# miniDMXplayer.net
KiCad netlist of a schematic drawn in EAGLE
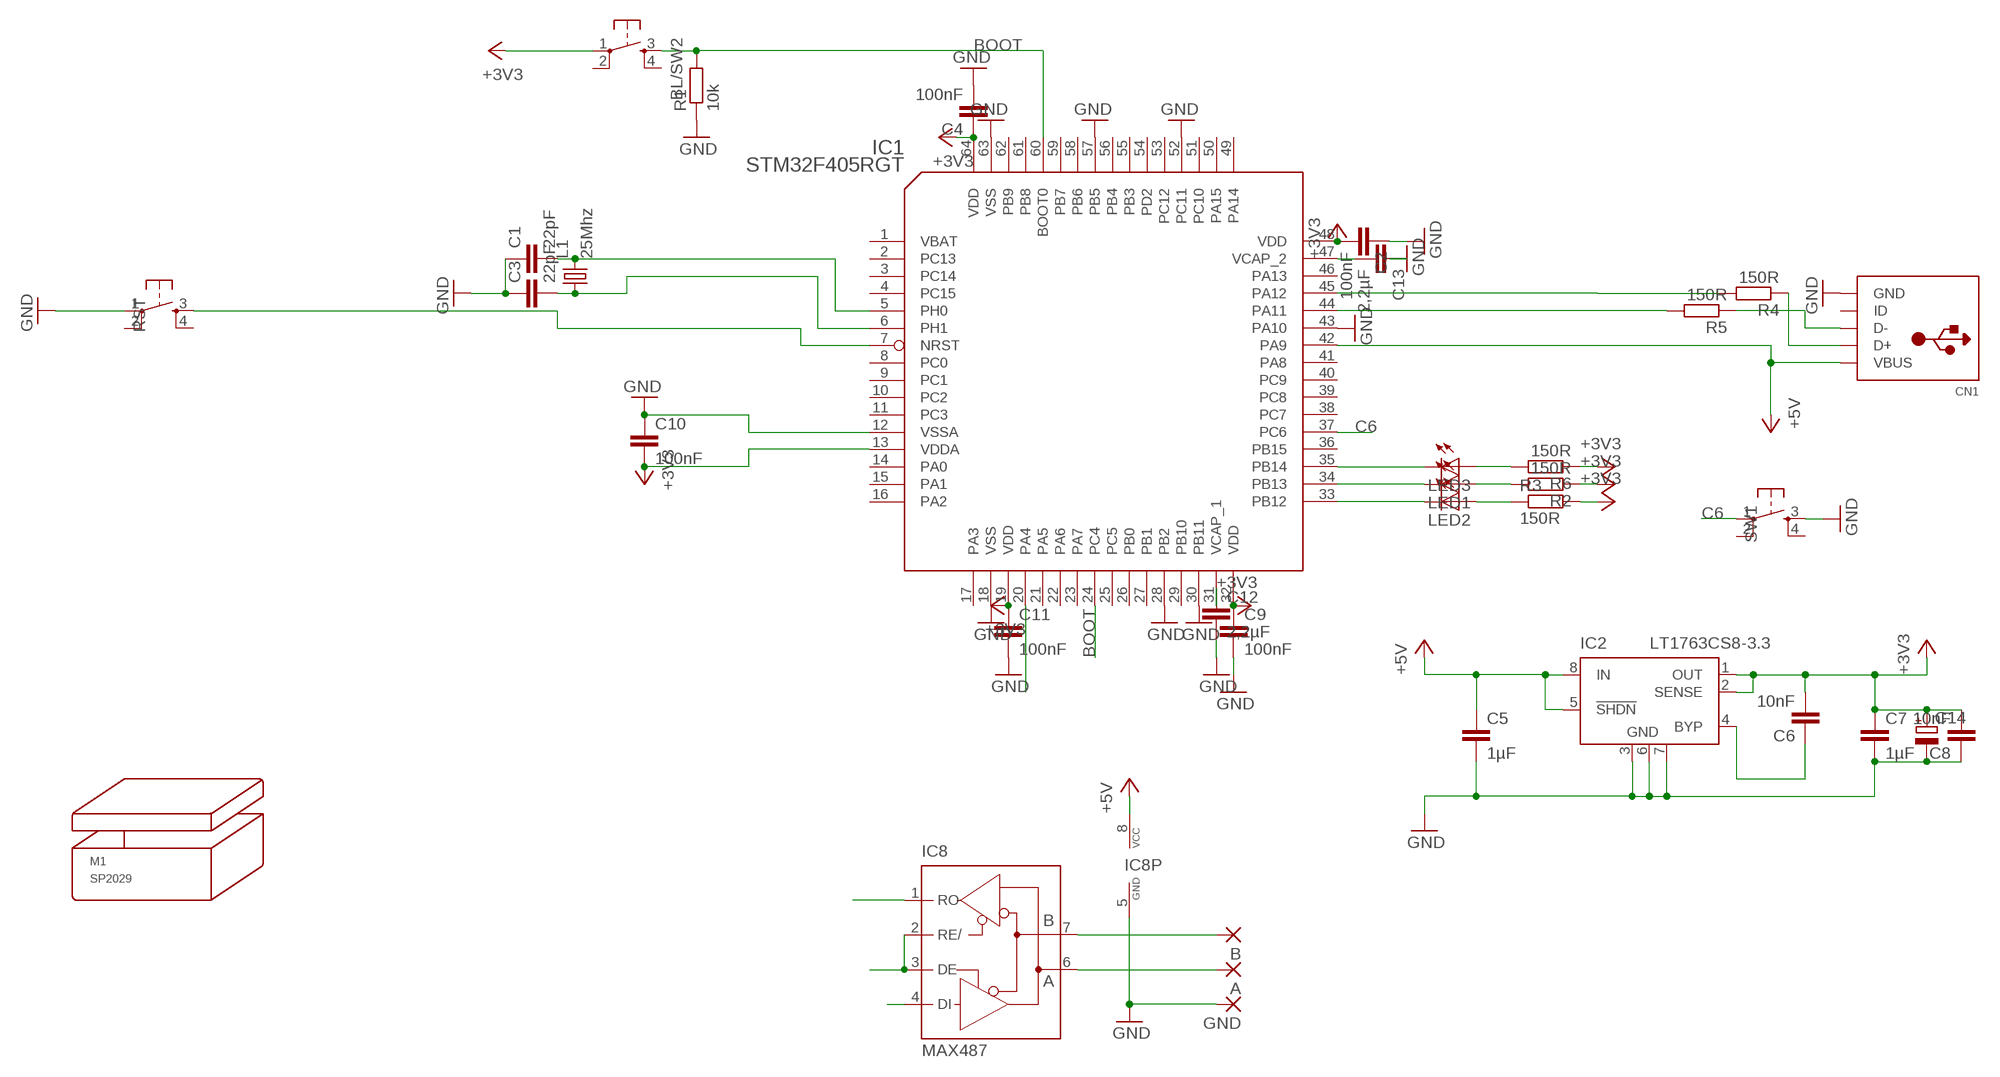
[diagram p0: schematic, sheet 1]

(export (version "E")
  (design (tool "Eeschema 10.0.6"))
  (components
    (comp (ref "A")
      (value "SMD5")
      (footprint "eagle-import:SMD2,54-5,08")
      (libsource (lib "eagle-import") (part "SMD5"))
    )
    (comp (ref "B")
      (value "SMD5")
      (footprint "eagle-import:SMD2,54-5,08")
      (libsource (lib "eagle-import") (part "SMD5"))
    )
    (comp (ref "BL/SW2")
      (value "DTSM-6")
      (footprint "eagle-import:DTSM-6")
      (libsource (lib "eagle-import") (part "DTSM-6"))
    )
    (comp (ref "C1")
      (value "22pF")
      (footprint "eagle-import:C0402")
      (libsource (lib "eagle-import") (part "C-EUC0402"))
    )
    (comp (ref "C2")
      (value "100nF")
      (footprint "eagle-import:C0402")
      (libsource (lib "eagle-import") (part "C-EUC0402"))
    )
    (comp (ref "C3")
      (value "22pF")
      (footprint "eagle-import:C0402")
      (libsource (lib "eagle-import") (part "C-EUC0402"))
    )
    (comp (ref "C4")
      (value "100nF")
      (footprint "eagle-import:C0402")
      (libsource (lib "eagle-import") (part "C-EUC0402"))
    )
    (comp (ref "C5")
      (value "1µF")
      (footprint "eagle-import:0805")
      (libsource (lib "eagle-import") (part "CAP0805"))
    )
    (comp (ref "C6")
      (value "10nF")
      (footprint "eagle-import:C0402")
      (libsource (lib "eagle-import") (part "C-EUC0402"))
    )
    (comp (ref "C7")
      (value "1µF")
      (footprint "eagle-import:0805")
      (libsource (lib "eagle-import") (part "CAP0805"))
    )
    (comp (ref "C8")
      (value "10nF")
      (footprint "eagle-import:C0402")
      (libsource (lib "eagle-import") (part "C-EUC0402"))
    )
    (comp (ref "C9")
      (value "100nF")
      (footprint "eagle-import:C0402")
      (libsource (lib "eagle-import") (part "C-EUC0402"))
    )
    (comp (ref "C10")
      (value "100nF")
      (footprint "eagle-import:C0402")
      (libsource (lib "eagle-import") (part "C-EUC0402"))
    )
    (comp (ref "C11")
      (value "100nF")
      (footprint "eagle-import:C0402")
      (libsource (lib "eagle-import") (part "C-EUC0402"))
    )
    (comp (ref "C12")
      (value "2,2µF")
      (footprint "eagle-import:0805")
      (libsource (lib "eagle-import") (part "CAP0805"))
    )
    (comp (ref "C13")
      (value "2,2µF")
      (footprint "eagle-import:0805")
      (libsource (lib "eagle-import") (part "CAP0805"))
    )
    (comp (ref "C14")
      (value "CPOL-EUSMCA")
      (footprint "eagle-import:SMC_A")
      (libsource (lib "eagle-import") (part "CPOL-EUSMCA"))
    )
    (comp (ref "CN1")
      (value "USBMINIB")
      (footprint "eagle-import:USB-MINIB")
      (libsource (lib "eagle-import") (part "USBMINIB"))
    )
    (comp (ref "GND")
      (value "SMD5")
      (footprint "eagle-import:SMD2,54-5,08")
      (libsource (lib "eagle-import") (part "SMD5"))
    )
    (comp (ref "IC1")
      (value "STM32F405RGT")
      (footprint "eagle-import:LQFP64")
      (libsource (lib "eagle-import") (part "STM32F405RTG"))
    )
    (comp (ref "IC2")
      (value "LT1763CS8-3.3")
      (footprint "eagle-import:SOIC8")
      (libsource (lib "eagle-import") (part "LT1763CS8-3.3"))
    )
    (comp (ref "IC8")
      (value "MAX487")
      (footprint "eagle-import:SO08")
      (fields (field (name "MF") "MAXIM") (field (name "MPN") "MAX481CSA"))
      (libsource (lib "eagle-import") (part "MAX481CSA"))
    )
    (comp (ref "L1")
      (value "25Mhz")
      (footprint "eagle-import:X22")
      (libsource (lib "eagle-import") (part "X22-OSCILLATOR"))
    )
    (comp (ref "LED1")
      (value "LED0603")
      (footprint "eagle-import:LED-0603")
      (libsource (lib "eagle-import") (part "LED0603"))
    )
    (comp (ref "LED2")
      (value "LED0603")
      (footprint "eagle-import:LED-0603")
      (libsource (lib "eagle-import") (part "LED0603"))
    )
    (comp (ref "LED3")
      (value "LED0603")
      (footprint "eagle-import:LED-0603")
      (libsource (lib "eagle-import") (part "LED0603"))
    )
    (comp (ref "M1")
      (value "SP2029")
      (footprint "eagle-import:SP2029")
      (libsource (lib "eagle-import") (part "SP2029"))
    )
    (comp (ref "R1")
      (value "10k")
      (footprint "eagle-import:R0402")
      (libsource (lib "eagle-import") (part "R-EU_R0402"))
    )
    (comp (ref "R2")
      (value "150R")
      (footprint "eagle-import:R0402")
      (libsource (lib "eagle-import") (part "R-EU_R0402"))
    )
    (comp (ref "R3")
      (value "150R")
      (footprint "eagle-import:R0402")
      (libsource (lib "eagle-import") (part "R-EU_R0402"))
    )
    (comp (ref "R4")
      (value "150R")
      (footprint "eagle-import:R0402")
      (libsource (lib "eagle-import") (part "R-EU_R0402"))
    )
    (comp (ref "R5")
      (value "150R")
      (footprint "eagle-import:R0402")
      (libsource (lib "eagle-import") (part "R-EU_R0402"))
    )
    (comp (ref "R6")
      (value "150R")
      (footprint "eagle-import:R0402")
      (libsource (lib "eagle-import") (part "R-EU_R0402"))
    )
    (comp (ref "RST")
      (value "DTSM-6")
      (footprint "eagle-import:DTSM-6")
      (libsource (lib "eagle-import") (part "DTSM-6"))
    )
    (comp (ref "SW1")
      (value "DTSM-6")
      (footprint "eagle-import:DTSM-6")
      (libsource (lib "eagle-import") (part "DTSM-6"))
    )
  )
  (nets
    (net (code "1") (name "+3V3") (class "Default")
      (node (ref "BL/SW2") (pin "1") (pinfunction "1_1") (pintype "passive"))
      (node (ref "C10") (pin "2") (pinfunction "2_2") (pintype "passive"))
      (node (ref "C11") (pin "1") (pinfunction "1_1") (pintype "passive"))
      (node (ref "C14") (pin "+") (pinfunction "+_+") (pintype "passive"))
      (node (ref "C2") (pin "2") (pinfunction "2_2") (pintype "passive"))
      (node (ref "C4") (pin "1") (pinfunction "1_1") (pintype "passive"))
      (node (ref "C6") (pin "2") (pinfunction "2_2") (pintype "passive"))
      (node (ref "C7") (pin "1") (pinfunction "1_1") (pintype "passive"))
      (node (ref "C8") (pin "2") (pinfunction "2_2") (pintype "passive"))
      (node (ref "C9") (pin "1") (pinfunction "1_1") (pintype "passive"))
      (node (ref "IC1") (pin "13") (pinfunction "VDDA_13") (pintype "power_in"))
      (node (ref "IC1") (pin "19") (pinfunction "VDD_19") (pintype "power_in"))
      (node (ref "IC1") (pin "32") (pinfunction "VDD_32") (pintype "power_in"))
      (node (ref "IC1") (pin "48") (pinfunction "VDD_48") (pintype "power_in"))
      (node (ref "IC1") (pin "64") (pinfunction "VDD_64") (pintype "power_in"))
      (node (ref "IC2") (pin "1") (pinfunction "OUT_1") (pintype "passive"))
      (node (ref "IC2") (pin "2") (pinfunction "SENSE_2") (pintype "input"))
      (node (ref "R2") (pin "1") (pinfunction "1_1") (pintype "passive"))
      (node (ref "R3") (pin "2") (pinfunction "2_2") (pintype "passive"))
      (node (ref "R6") (pin "1") (pinfunction "1_1") (pintype "passive"))
    )
    (net (code "2") (name "+5V") (class "Default")
      (node (ref "C5") (pin "1") (pinfunction "1_1") (pintype "passive"))
      (node (ref "CN1") (pin "VBUS") (pinfunction "VBUS_VBUS") (pintype "power_in"))
      (node (ref "IC1") (pin "42") (pinfunction "PA9_42") (pintype "bidirectional"))
      (node (ref "IC2") (pin "5") (pinfunction "~{SHDN}_5") (pintype "input"))
      (node (ref "IC2") (pin "8") (pinfunction "IN_8") (pintype "input"))
      (node (ref "IC8") (pin "8") (pinfunction "VCC_8") (pintype "power_in"))
    )
    (net (code "3") (name "/BOOT") (class "Default")
      (node (ref "BL/SW2") (pin "3") (pinfunction "3_3") (pintype "passive"))
      (node (ref "IC1") (pin "24") (pinfunction "PC4_24") (pintype "bidirectional"))
      (node (ref "IC1") (pin "60") (pinfunction "BOOT0_60") (pintype "bidirectional"))
      (node (ref "R1") (pin "2") (pinfunction "2_2") (pintype "passive"))
    )
    (net (code "4") (name "/C6") (class "Default")
      (node (ref "IC1") (pin "37") (pinfunction "PC6_37") (pintype "bidirectional"))
      (node (ref "SW1") (pin "1") (pinfunction "1_1") (pintype "passive"))
    )
    (net (code "5") (name "/VBAT") (class "Default")
      (node (ref "IC1") (pin "1") (pinfunction "VBAT_1") (pintype "power_in"))
    )
    (net (code "6") (name "GND") (class "Default")
      (node (ref "C1") (pin "1") (pinfunction "1_1") (pintype "passive"))
      (node (ref "C10") (pin "1") (pinfunction "1_1") (pintype "passive"))
      (node (ref "C11") (pin "2") (pinfunction "2_2") (pintype "passive"))
      (node (ref "C12") (pin "2") (pinfunction "2_2") (pintype "passive"))
      (node (ref "C13") (pin "1") (pinfunction "1_1") (pintype "passive"))
      (node (ref "C14") (pin "-") (pinfunction "-_-") (pintype "passive"))
      (node (ref "C2") (pin "1") (pinfunction "1_1") (pintype "passive"))
      (node (ref "C3") (pin "1") (pinfunction "1_1") (pintype "passive"))
      (node (ref "C4") (pin "2") (pinfunction "2_2") (pintype "passive"))
      (node (ref "C5") (pin "2") (pinfunction "2_2") (pintype "passive"))
      (node (ref "C7") (pin "2") (pinfunction "2_2") (pintype "passive"))
      (node (ref "C8") (pin "1") (pinfunction "1_1") (pintype "passive"))
      (node (ref "C9") (pin "2") (pinfunction "2_2") (pintype "passive"))
      (node (ref "CN1") (pin "GND") (pinfunction "GND_GND") (pintype "power_in"))
      (node (ref "GND") (pin "1") (pinfunction "P_1") (pintype "passive"))
      (node (ref "IC1") (pin "12") (pinfunction "VSSA_12") (pintype "power_in"))
      (node (ref "IC1") (pin "18") (pinfunction "VSS_18") (pintype "power_in"))
      (node (ref "IC1") (pin "28") (pinfunction "PB2_28") (pintype "bidirectional"))
      (node (ref "IC1") (pin "30") (pinfunction "PB11_30") (pintype "bidirectional"))
      (node (ref "IC1") (pin "43") (pinfunction "PA10_43") (pintype "bidirectional"))
      (node (ref "IC1") (pin "52") (pinfunction "PC11_52") (pintype "bidirectional"))
      (node (ref "IC1") (pin "57") (pinfunction "PB5_57") (pintype "bidirectional"))
      (node (ref "IC1") (pin "63") (pinfunction "VSS_63") (pintype "power_in"))
      (node (ref "IC2") (pin "3") (pinfunction "GND_3") (pintype "power_in"))
      (node (ref "IC2") (pin "6") (pinfunction "GND_6") (pintype "power_in"))
      (node (ref "IC2") (pin "7") (pinfunction "GND_7") (pintype "power_in"))
      (node (ref "IC8") (pin "5") (pinfunction "GND_5") (pintype "power_in"))
      (node (ref "R1") (pin "1") (pinfunction "1_1") (pintype "passive"))
      (node (ref "RST") (pin "1") (pinfunction "1_1") (pintype "passive"))
      (node (ref "SW1") (pin "3") (pinfunction "3_3") (pintype "passive"))
    )
    (net (code "7") (name "Net-(A-P)") (class "Default")
      (node (ref "A") (pin "1") (pinfunction "P_1") (pintype "passive"))
      (node (ref "IC8") (pin "6") (pinfunction "A_6") (pintype "passive"))
    )
    (net (code "8") (name "Net-(B-P)") (class "Default")
      (node (ref "B") (pin "1") (pinfunction "P_1") (pintype "passive"))
      (node (ref "IC8") (pin "7") (pinfunction "B_7") (pintype "passive"))
    )
    (net (code "9") (name "Net-(CN1-PadD+)") (class "Default")
      (node (ref "CN1") (pin "D+") (pinfunction "D+_D+") (pintype "bidirectional"))
      (node (ref "R4") (pin "1") (pinfunction "1_1") (pintype "passive"))
    )
    (net (code "10") (name "Net-(CN1-PadD-)") (class "Default")
      (node (ref "CN1") (pin "D-") (pinfunction "D-_D-") (pintype "bidirectional"))
      (node (ref "R5") (pin "1") (pinfunction "1_1") (pintype "passive"))
    )
    (net (code "11") (name "Net-(IC1-NRST)") (class "Default")
      (node (ref "IC1") (pin "7") (pinfunction "NRST_7") (pintype "input"))
      (node (ref "RST") (pin "3") (pinfunction "3_3") (pintype "passive"))
    )
    (net (code "12") (name "Net-(IC1-PA11)") (class "Default")
      (node (ref "IC1") (pin "44") (pinfunction "PA11_44") (pintype "bidirectional"))
      (node (ref "R5") (pin "2") (pinfunction "2_2") (pintype "passive"))
    )
    (net (code "13") (name "Net-(IC1-PA12)") (class "Default")
      (node (ref "IC1") (pin "45") (pinfunction "PA12_45") (pintype "bidirectional"))
      (node (ref "R4") (pin "2") (pinfunction "2_2") (pintype "passive"))
    )
    (net (code "14") (name "Net-(IC1-PB12)") (class "Default")
      (node (ref "IC1") (pin "33") (pinfunction "PB12_33") (pintype "bidirectional"))
      (node (ref "LED2") (pin "C") (pinfunction "C_C") (pintype "passive"))
    )
    (net (code "15") (name "Net-(IC1-PB13)") (class "Default")
      (node (ref "IC1") (pin "34") (pinfunction "PB13_34") (pintype "bidirectional"))
      (node (ref "LED1") (pin "C") (pinfunction "C_C") (pintype "passive"))
    )
    (net (code "16") (name "Net-(IC1-PB14)") (class "Default")
      (node (ref "IC1") (pin "35") (pinfunction "PB14_35") (pintype "bidirectional"))
      (node (ref "LED3") (pin "C") (pinfunction "C_C") (pintype "passive"))
    )
    (net (code "17") (name "Net-(IC1-PH0)") (class "Default")
      (node (ref "C1") (pin "2") (pinfunction "2_2") (pintype "passive"))
      (node (ref "IC1") (pin "5") (pinfunction "PH0_5") (pintype "bidirectional"))
      (node (ref "L1") (pin "3") (pinfunction "2_3") (pintype "passive"))
    )
    (net (code "18") (name "Net-(IC1-PH1)") (class "Default")
      (node (ref "C3") (pin "2") (pinfunction "2_2") (pintype "passive"))
      (node (ref "IC1") (pin "6") (pinfunction "PH1_6") (pintype "bidirectional"))
      (node (ref "L1") (pin "1") (pinfunction "1_1") (pintype "passive"))
    )
    (net (code "19") (name "Net-(IC1-VCAP_1)") (class "Default")
      (node (ref "C12") (pin "1") (pinfunction "1_1") (pintype "passive"))
      (node (ref "IC1") (pin "31") (pinfunction "VCAP_1_31") (pintype "passive"))
    )
    (net (code "20") (name "Net-(IC1-VCAP_2)") (class "Default")
      (node (ref "C13") (pin "2") (pinfunction "2_2") (pintype "passive"))
      (node (ref "IC1") (pin "47") (pinfunction "VCAP_2_47") (pintype "passive"))
    )
    (net (code "21") (name "Net-(IC2-BYP)") (class "Default")
      (node (ref "C6") (pin "1") (pinfunction "1_1") (pintype "passive"))
      (node (ref "IC2") (pin "4") (pinfunction "BYP_4") (pintype "input"))
    )
    (net (code "22") (name "Net-(IC8A-DE)") (class "Default")
      (node (ref "IC8") (pin "2") (pinfunction "RE/_2") (pintype "input"))
      (node (ref "IC8") (pin "3") (pinfunction "DE_3") (pintype "input"))
    )
    (net (code "23") (name "Net-(LED1-PadA)") (class "Default")
      (node (ref "LED1") (pin "A") (pinfunction "A_A") (pintype "passive"))
      (node (ref "R2") (pin "2") (pinfunction "2_2") (pintype "passive"))
    )
    (net (code "24") (name "Net-(LED2-PadA)") (class "Default")
      (node (ref "LED2") (pin "A") (pinfunction "A_A") (pintype "passive"))
      (node (ref "R3") (pin "1") (pinfunction "1_1") (pintype "passive"))
    )
    (net (code "25") (name "Net-(LED3-PadA)") (class "Default")
      (node (ref "LED3") (pin "A") (pinfunction "A_A") (pintype "passive"))
      (node (ref "R6") (pin "2") (pinfunction "2_2") (pintype "passive"))
    )
    (net (code "26") (name "unconnected-(BL/SW2-Pad2)") (class "Default")
      (node (ref "BL/SW2") (pin "2") (pinfunction "2_2") (pintype "passive"))
    )
    (net (code "27") (name "unconnected-(BL/SW2-Pad4)") (class "Default")
      (node (ref "BL/SW2") (pin "4") (pinfunction "4_4") (pintype "passive"))
    )
    (net (code "28") (name "unconnected-(CN1-PadID)") (class "Default")
      (node (ref "CN1") (pin "ID") (pinfunction "ID_ID") (pintype "bidirectional"))
    )
    (net (code "29") (name "unconnected-(IC1-PA0-Pad14)") (class "Default")
      (node (ref "IC1") (pin "14") (pinfunction "PA0_14") (pintype "bidirectional"))
    )
    (net (code "30") (name "unconnected-(IC1-PA1-Pad15)") (class "Default")
      (node (ref "IC1") (pin "15") (pinfunction "PA1_15") (pintype "bidirectional"))
    )
    (net (code "31") (name "unconnected-(IC1-PA2-Pad16)") (class "Default")
      (node (ref "IC1") (pin "16") (pinfunction "PA2_16") (pintype "bidirectional"))
    )
    (net (code "32") (name "unconnected-(IC1-PA3-Pad17)") (class "Default")
      (node (ref "IC1") (pin "17") (pinfunction "PA3_17") (pintype "bidirectional"))
    )
    (net (code "33") (name "unconnected-(IC1-PA4-Pad20)") (class "Default")
      (node (ref "IC1") (pin "20") (pinfunction "PA4_20") (pintype "bidirectional"))
    )
    (net (code "34") (name "unconnected-(IC1-PA5-Pad21)") (class "Default")
      (node (ref "IC1") (pin "21") (pinfunction "PA5_21") (pintype "bidirectional"))
    )
    (net (code "35") (name "unconnected-(IC1-PA6-Pad22)") (class "Default")
      (node (ref "IC1") (pin "22") (pinfunction "PA6_22") (pintype "bidirectional"))
    )
    (net (code "36") (name "unconnected-(IC1-PA7-Pad23)") (class "Default")
      (node (ref "IC1") (pin "23") (pinfunction "PA7_23") (pintype "bidirectional"))
    )
    (net (code "37") (name "unconnected-(IC1-PA8-Pad41)") (class "Default")
      (node (ref "IC1") (pin "41") (pinfunction "PA8_41") (pintype "bidirectional"))
    )
    (net (code "38") (name "unconnected-(IC1-PA13-Pad46)") (class "Default")
      (node (ref "IC1") (pin "46") (pinfunction "PA13_46") (pintype "bidirectional"))
    )
    (net (code "39") (name "unconnected-(IC1-PA14-Pad49)") (class "Default")
      (node (ref "IC1") (pin "49") (pinfunction "PA14_49") (pintype "bidirectional"))
    )
    (net (code "40") (name "unconnected-(IC1-PA15-Pad50)") (class "Default")
      (node (ref "IC1") (pin "50") (pinfunction "PA15_50") (pintype "bidirectional"))
    )
    (net (code "41") (name "unconnected-(IC1-PB0-Pad26)") (class "Default")
      (node (ref "IC1") (pin "26") (pinfunction "PB0_26") (pintype "bidirectional"))
    )
    (net (code "42") (name "unconnected-(IC1-PB1-Pad27)") (class "Default")
      (node (ref "IC1") (pin "27") (pinfunction "PB1_27") (pintype "bidirectional"))
    )
    (net (code "43") (name "unconnected-(IC1-PB3-Pad55)") (class "Default")
      (node (ref "IC1") (pin "55") (pinfunction "PB3_55") (pintype "bidirectional"))
    )
    (net (code "44") (name "unconnected-(IC1-PB4-Pad56)") (class "Default")
      (node (ref "IC1") (pin "56") (pinfunction "PB4_56") (pintype "bidirectional"))
    )
    (net (code "45") (name "unconnected-(IC1-PB6-Pad58)") (class "Default")
      (node (ref "IC1") (pin "58") (pinfunction "PB6_58") (pintype "bidirectional"))
    )
    (net (code "46") (name "unconnected-(IC1-PB7-Pad59)") (class "Default")
      (node (ref "IC1") (pin "59") (pinfunction "PB7_59") (pintype "bidirectional"))
    )
    (net (code "47") (name "unconnected-(IC1-PB8-Pad61)") (class "Default")
      (node (ref "IC1") (pin "61") (pinfunction "PB8_61") (pintype "bidirectional"))
    )
    (net (code "48") (name "unconnected-(IC1-PB9-Pad62)") (class "Default")
      (node (ref "IC1") (pin "62") (pinfunction "PB9_62") (pintype "bidirectional"))
    )
    (net (code "49") (name "unconnected-(IC1-PB10-Pad29)") (class "Default")
      (node (ref "IC1") (pin "29") (pinfunction "PB10_29") (pintype "bidirectional"))
    )
    (net (code "50") (name "unconnected-(IC1-PB15-Pad36)") (class "Default")
      (node (ref "IC1") (pin "36") (pinfunction "PB15_36") (pintype "bidirectional"))
    )
    (net (code "51") (name "unconnected-(IC1-PC0-Pad8)") (class "Default")
      (node (ref "IC1") (pin "8") (pinfunction "PC0_8") (pintype "bidirectional"))
    )
    (net (code "52") (name "unconnected-(IC1-PC1-Pad9)") (class "Default")
      (node (ref "IC1") (pin "9") (pinfunction "PC1_9") (pintype "bidirectional"))
    )
    (net (code "53") (name "unconnected-(IC1-PC2-Pad10)") (class "Default")
      (node (ref "IC1") (pin "10") (pinfunction "PC2_10") (pintype "bidirectional"))
    )
    (net (code "54") (name "unconnected-(IC1-PC3-Pad11)") (class "Default")
      (node (ref "IC1") (pin "11") (pinfunction "PC3_11") (pintype "bidirectional"))
    )
    (net (code "55") (name "unconnected-(IC1-PC5-Pad25)") (class "Default")
      (node (ref "IC1") (pin "25") (pinfunction "PC5_25") (pintype "bidirectional"))
    )
    (net (code "56") (name "unconnected-(IC1-PC7-Pad38)") (class "Default")
      (node (ref "IC1") (pin "38") (pinfunction "PC7_38") (pintype "bidirectional"))
    )
    (net (code "57") (name "unconnected-(IC1-PC8-Pad39)") (class "Default")
      (node (ref "IC1") (pin "39") (pinfunction "PC8_39") (pintype "bidirectional"))
    )
    (net (code "58") (name "unconnected-(IC1-PC9-Pad40)") (class "Default")
      (node (ref "IC1") (pin "40") (pinfunction "PC9_40") (pintype "bidirectional"))
    )
    (net (code "59") (name "unconnected-(IC1-PC10-Pad51)") (class "Default")
      (node (ref "IC1") (pin "51") (pinfunction "PC10_51") (pintype "bidirectional"))
    )
    (net (code "60") (name "unconnected-(IC1-PC12-Pad53)") (class "Default")
      (node (ref "IC1") (pin "53") (pinfunction "PC12_53") (pintype "bidirectional"))
    )
    (net (code "61") (name "unconnected-(IC1-PC13-Pad2)") (class "Default")
      (node (ref "IC1") (pin "2") (pinfunction "PC13_2") (pintype "bidirectional"))
    )
    (net (code "62") (name "unconnected-(IC1-PC14-Pad3)") (class "Default")
      (node (ref "IC1") (pin "3") (pinfunction "PC14_3") (pintype "bidirectional"))
    )
    (net (code "63") (name "unconnected-(IC1-PC15-Pad4)") (class "Default")
      (node (ref "IC1") (pin "4") (pinfunction "PC15_4") (pintype "bidirectional"))
    )
    (net (code "64") (name "unconnected-(IC1-PD2-Pad54)") (class "Default")
      (node (ref "IC1") (pin "54") (pinfunction "PD2_54") (pintype "bidirectional"))
    )
    (net (code "65") (name "unconnected-(IC8A-DI-Pad4)") (class "Default")
      (node (ref "IC8") (pin "4") (pinfunction "DI_4") (pintype "input"))
    )
    (net (code "66") (name "unconnected-(IC8A-RO-Pad1)") (class "Default")
      (node (ref "IC8") (pin "1") (pinfunction "RO_1") (pintype "output"))
    )
    (net (code "67") (name "unconnected-(RST-Pad2)") (class "Default")
      (node (ref "RST") (pin "2") (pinfunction "2_2") (pintype "passive"))
    )
    (net (code "68") (name "unconnected-(RST-Pad4)") (class "Default")
      (node (ref "RST") (pin "4") (pinfunction "4_4") (pintype "passive"))
    )
    (net (code "69") (name "unconnected-(SW1-Pad2)") (class "Default")
      (node (ref "SW1") (pin "2") (pinfunction "2_2") (pintype "passive"))
    )
    (net (code "70") (name "unconnected-(SW1-Pad4)") (class "Default")
      (node (ref "SW1") (pin "4") (pinfunction "4_4") (pintype "passive"))
    )
  )
)
